# u10-normal.net
KiCad netlist of a schematic drawn in EAGLE
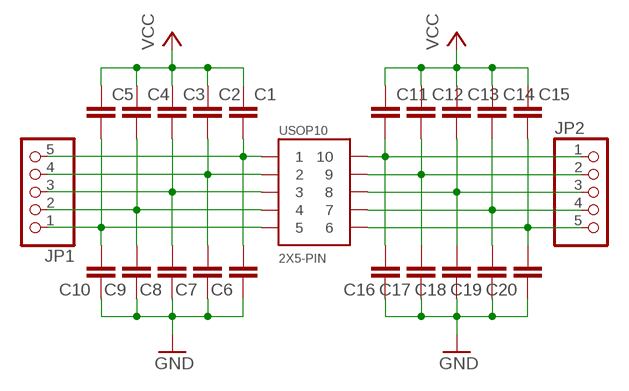
[diagram p0: schematic, sheet 1]

(export (version "E")
  (design (tool "Eeschema 10.0.6"))
  (components
    (comp (ref "C1")
      (value "C-EUC0603")
      (footprint "eagle-import:C0603")
      (libsource (lib "eagle-import") (part "C-EUC0603"))
    )
    (comp (ref "C2")
      (value "C-EUC0603")
      (footprint "eagle-import:C0603")
      (libsource (lib "eagle-import") (part "C-EUC0603"))
    )
    (comp (ref "C3")
      (value "C-EUC0603")
      (footprint "eagle-import:C0603")
      (libsource (lib "eagle-import") (part "C-EUC0603"))
    )
    (comp (ref "C4")
      (value "C-EUC0603")
      (footprint "eagle-import:C0603")
      (libsource (lib "eagle-import") (part "C-EUC0603"))
    )
    (comp (ref "C5")
      (value "C-EUC0603")
      (footprint "eagle-import:C0603")
      (libsource (lib "eagle-import") (part "C-EUC0603"))
    )
    (comp (ref "C6")
      (value "C-EUC0805")
      (footprint "eagle-import:C0805")
      (libsource (lib "eagle-import") (part "C-EUC0805"))
    )
    (comp (ref "C7")
      (value "C-EUC0805")
      (footprint "eagle-import:C0805")
      (libsource (lib "eagle-import") (part "C-EUC0805"))
    )
    (comp (ref "C8")
      (value "C-EUC0805")
      (footprint "eagle-import:C0805")
      (libsource (lib "eagle-import") (part "C-EUC0805"))
    )
    (comp (ref "C9")
      (value "C-EUC0805")
      (footprint "eagle-import:C0805")
      (libsource (lib "eagle-import") (part "C-EUC0805"))
    )
    (comp (ref "C10")
      (value "C-EUC0805")
      (footprint "eagle-import:C0805")
      (libsource (lib "eagle-import") (part "C-EUC0805"))
    )
    (comp (ref "C11")
      (value "C-EUC0603")
      (footprint "eagle-import:C0603")
      (libsource (lib "eagle-import") (part "C-EUC0603"))
    )
    (comp (ref "C12")
      (value "C-EUC0603")
      (footprint "eagle-import:C0603")
      (libsource (lib "eagle-import") (part "C-EUC0603"))
    )
    (comp (ref "C13")
      (value "C-EUC0603")
      (footprint "eagle-import:C0603")
      (libsource (lib "eagle-import") (part "C-EUC0603"))
    )
    (comp (ref "C14")
      (value "C-EUC0603")
      (footprint "eagle-import:C0603")
      (libsource (lib "eagle-import") (part "C-EUC0603"))
    )
    (comp (ref "C15")
      (value "C-EUC0603")
      (footprint "eagle-import:C0603")
      (libsource (lib "eagle-import") (part "C-EUC0603"))
    )
    (comp (ref "C16")
      (value "C-EUC0805")
      (footprint "eagle-import:C0805")
      (libsource (lib "eagle-import") (part "C-EUC0805"))
    )
    (comp (ref "C17")
      (value "C-EUC0805")
      (footprint "eagle-import:C0805")
      (libsource (lib "eagle-import") (part "C-EUC0805"))
    )
    (comp (ref "C18")
      (value "C-EUC0805")
      (footprint "eagle-import:C0805")
      (libsource (lib "eagle-import") (part "C-EUC0805"))
    )
    (comp (ref "C19")
      (value "C-EUC0805")
      (footprint "eagle-import:C0805")
      (libsource (lib "eagle-import") (part "C-EUC0805"))
    )
    (comp (ref "C20")
      (value "C-EUC0805")
      (footprint "eagle-import:C0805")
      (libsource (lib "eagle-import") (part "C-EUC0805"))
    )
    (comp (ref "JP1")
      (value "PINHD-1X5")
      (footprint "eagle-import:1X05")
      (libsource (lib "eagle-import") (part "PINHD-1X5"))
    )
    (comp (ref "JP2")
      (value "PINHD-1X5")
      (footprint "eagle-import:1X05")
      (libsource (lib "eagle-import") (part "PINHD-1X5"))
    )
    (comp (ref "USOP10")
      (value "2X5-PIN")
      (footprint "eagle-import:USOP10")
      (libsource (lib "eagle-import") (part "2X5-PIN"))
    )
  )
  (nets
    (net (code "1") (name "GND") (class "Default")
      (node (ref "C10") (pin "1") (pinfunction "1_1") (pintype "passive"))
      (node (ref "C16") (pin "1") (pinfunction "1_1") (pintype "passive"))
      (node (ref "C17") (pin "1") (pinfunction "1_1") (pintype "passive"))
      (node (ref "C18") (pin "1") (pinfunction "1_1") (pintype "passive"))
      (node (ref "C19") (pin "1") (pinfunction "1_1") (pintype "passive"))
      (node (ref "C20") (pin "1") (pinfunction "1_1") (pintype "passive"))
      (node (ref "C6") (pin "1") (pinfunction "1_1") (pintype "passive"))
      (node (ref "C7") (pin "1") (pinfunction "1_1") (pintype "passive"))
      (node (ref "C8") (pin "1") (pinfunction "1_1") (pintype "passive"))
      (node (ref "C9") (pin "1") (pinfunction "1_1") (pintype "passive"))
    )
    (net (code "2") (name "Net-(USOP10-1)") (class "Default")
      (node (ref "C1") (pin "2") (pinfunction "2_2") (pintype "passive"))
      (node (ref "C6") (pin "2") (pinfunction "2_2") (pintype "passive"))
      (node (ref "JP1") (pin "5") (pinfunction "5_5") (pintype "passive"))
      (node (ref "USOP10") (pin "P$1") (pinfunction "1_P$1") (pintype "bidirectional"))
    )
    (net (code "3") (name "Net-(USOP10-2)") (class "Default")
      (node (ref "C2") (pin "2") (pinfunction "2_2") (pintype "passive"))
      (node (ref "C7") (pin "2") (pinfunction "2_2") (pintype "passive"))
      (node (ref "JP1") (pin "4") (pinfunction "4_4") (pintype "passive"))
      (node (ref "USOP10") (pin "P$2") (pinfunction "2_P$2") (pintype "bidirectional"))
    )
    (net (code "4") (name "Net-(USOP10-3)") (class "Default")
      (node (ref "C3") (pin "2") (pinfunction "2_2") (pintype "passive"))
      (node (ref "C8") (pin "2") (pinfunction "2_2") (pintype "passive"))
      (node (ref "JP1") (pin "3") (pinfunction "3_3") (pintype "passive"))
      (node (ref "USOP10") (pin "P$3") (pinfunction "3_P$3") (pintype "bidirectional"))
    )
    (net (code "5") (name "Net-(USOP10-4)") (class "Default")
      (node (ref "C4") (pin "2") (pinfunction "2_2") (pintype "passive"))
      (node (ref "C9") (pin "2") (pinfunction "2_2") (pintype "passive"))
      (node (ref "JP1") (pin "2") (pinfunction "2_2") (pintype "passive"))
      (node (ref "USOP10") (pin "P$4") (pinfunction "4_P$4") (pintype "bidirectional"))
    )
    (net (code "6") (name "Net-(USOP10-5)") (class "Default")
      (node (ref "C10") (pin "2") (pinfunction "2_2") (pintype "passive"))
      (node (ref "C5") (pin "2") (pinfunction "2_2") (pintype "passive"))
      (node (ref "JP1") (pin "1") (pinfunction "1_1") (pintype "passive"))
      (node (ref "USOP10") (pin "P$5") (pinfunction "5_P$5") (pintype "bidirectional"))
    )
    (net (code "7") (name "Net-(USOP10-6)") (class "Default")
      (node (ref "C15") (pin "2") (pinfunction "2_2") (pintype "passive"))
      (node (ref "C20") (pin "2") (pinfunction "2_2") (pintype "passive"))
      (node (ref "JP2") (pin "5") (pinfunction "5_5") (pintype "passive"))
      (node (ref "USOP10") (pin "P$6") (pinfunction "6_P$6") (pintype "bidirectional"))
    )
    (net (code "8") (name "Net-(USOP10-7)") (class "Default")
      (node (ref "C14") (pin "2") (pinfunction "2_2") (pintype "passive"))
      (node (ref "C19") (pin "2") (pinfunction "2_2") (pintype "passive"))
      (node (ref "JP2") (pin "4") (pinfunction "4_4") (pintype "passive"))
      (node (ref "USOP10") (pin "P$7") (pinfunction "7_P$7") (pintype "bidirectional"))
    )
    (net (code "9") (name "Net-(USOP10-8)") (class "Default")
      (node (ref "C13") (pin "2") (pinfunction "2_2") (pintype "passive"))
      (node (ref "C18") (pin "2") (pinfunction "2_2") (pintype "passive"))
      (node (ref "JP2") (pin "3") (pinfunction "3_3") (pintype "passive"))
      (node (ref "USOP10") (pin "P$8") (pinfunction "8_P$8") (pintype "bidirectional"))
    )
    (net (code "10") (name "Net-(USOP10-9)") (class "Default")
      (node (ref "C12") (pin "2") (pinfunction "2_2") (pintype "passive"))
      (node (ref "C17") (pin "2") (pinfunction "2_2") (pintype "passive"))
      (node (ref "JP2") (pin "2") (pinfunction "2_2") (pintype "passive"))
      (node (ref "USOP10") (pin "P$9") (pinfunction "9_P$9") (pintype "bidirectional"))
    )
    (net (code "11") (name "Net-(USOP10-10)") (class "Default")
      (node (ref "C11") (pin "2") (pinfunction "2_2") (pintype "passive"))
      (node (ref "C16") (pin "2") (pinfunction "2_2") (pintype "passive"))
      (node (ref "JP2") (pin "1") (pinfunction "1_1") (pintype "passive"))
      (node (ref "USOP10") (pin "P$10") (pinfunction "10_P$10") (pintype "bidirectional"))
    )
    (net (code "12") (name "VCC") (class "Default")
      (node (ref "C1") (pin "1") (pinfunction "1_1") (pintype "passive"))
      (node (ref "C11") (pin "1") (pinfunction "1_1") (pintype "passive"))
      (node (ref "C12") (pin "1") (pinfunction "1_1") (pintype "passive"))
      (node (ref "C13") (pin "1") (pinfunction "1_1") (pintype "passive"))
      (node (ref "C14") (pin "1") (pinfunction "1_1") (pintype "passive"))
      (node (ref "C15") (pin "1") (pinfunction "1_1") (pintype "passive"))
      (node (ref "C2") (pin "1") (pinfunction "1_1") (pintype "passive"))
      (node (ref "C3") (pin "1") (pinfunction "1_1") (pintype "passive"))
      (node (ref "C4") (pin "1") (pinfunction "1_1") (pintype "passive"))
      (node (ref "C5") (pin "1") (pinfunction "1_1") (pintype "passive"))
    )
  )
)
